# mippe_base.net
KiCad netlist of a schematic drawn in EAGLE
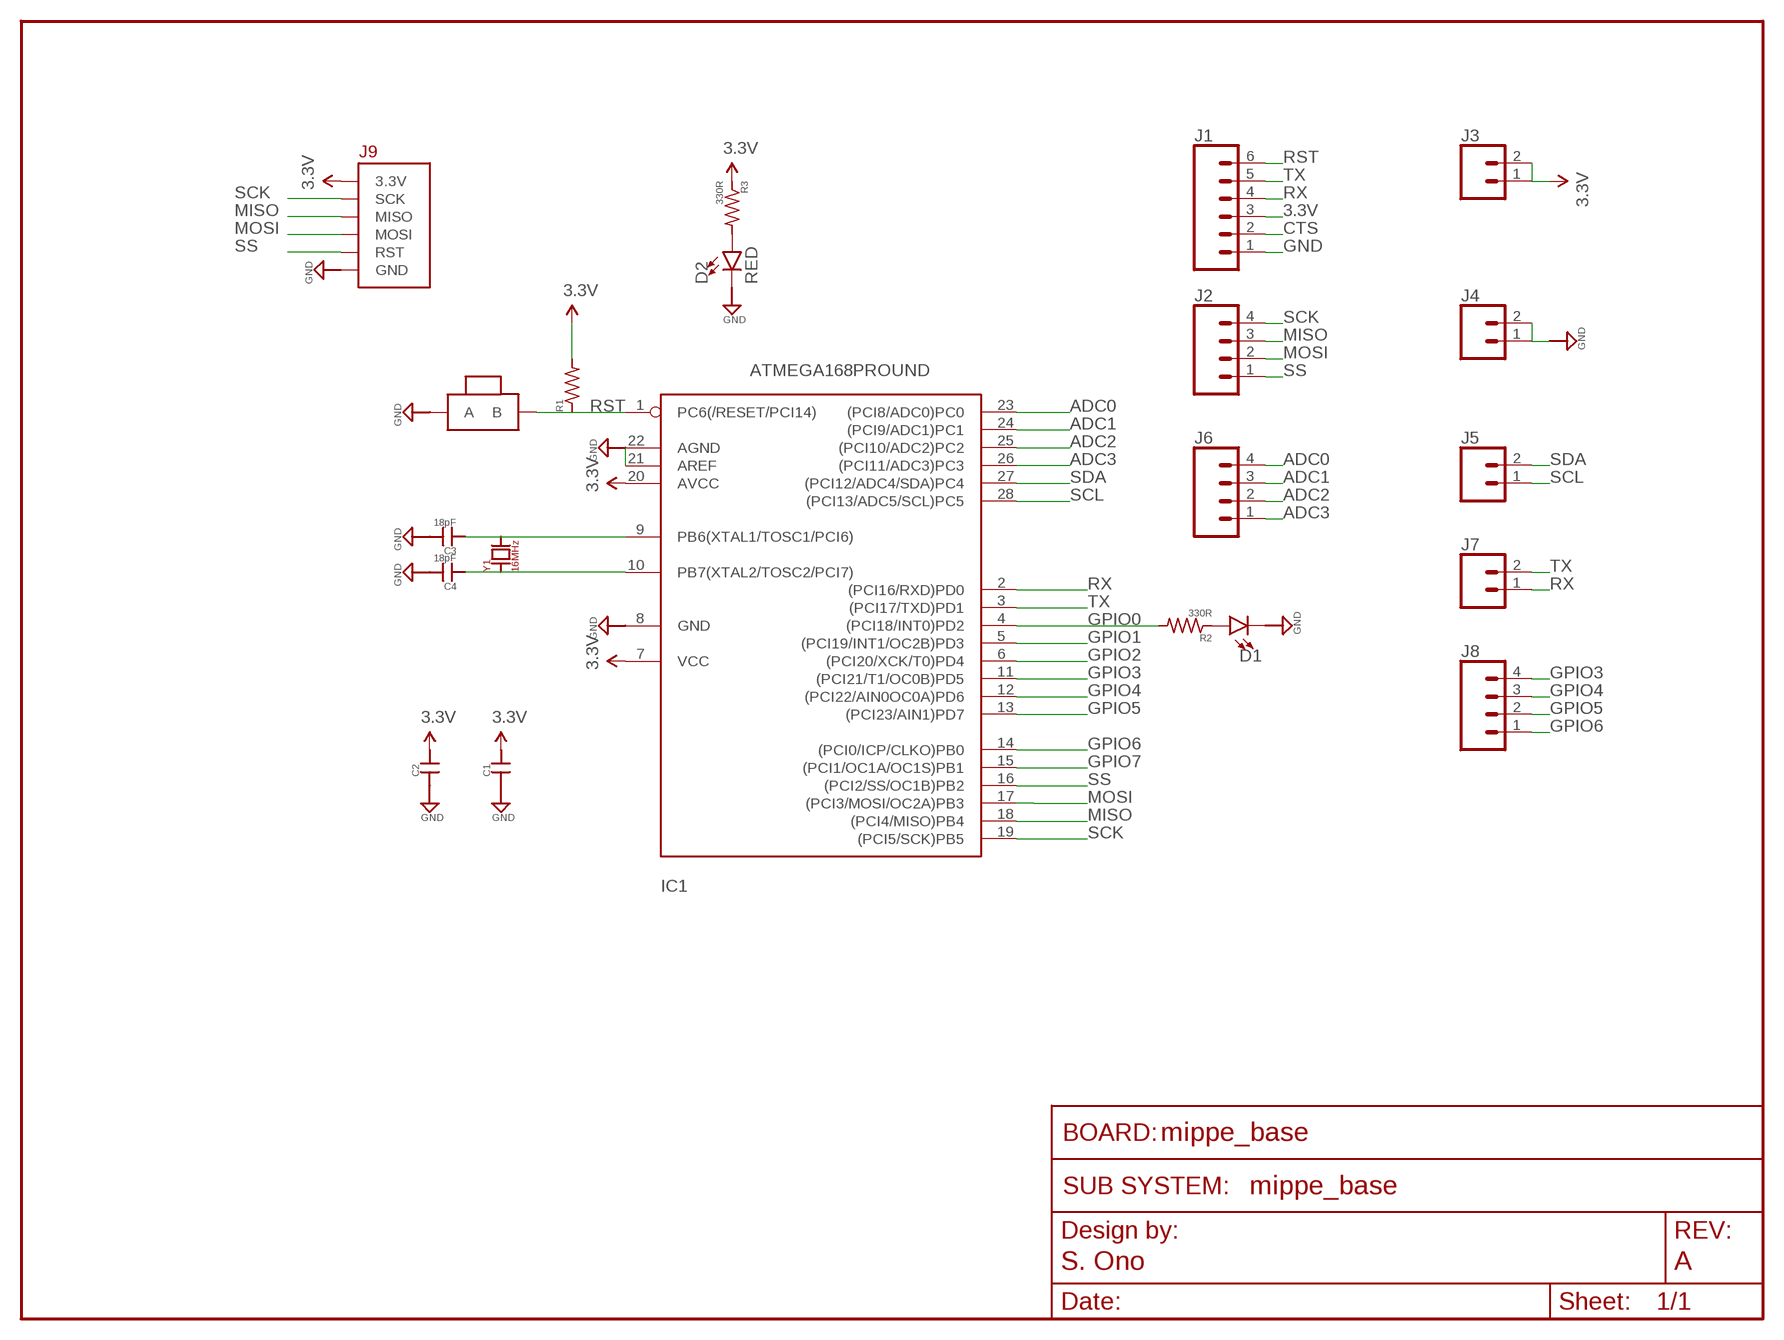
[diagram p0: schematic, sheet 1]

(export (version "E")
  (design (tool "Eeschema 10.0.6"))
  (components
    (comp (ref "C1")
      (value "CAP0603-CAP")
      (footprint "eagle-import:0603-CAP")
      (libsource (lib "eagle-import") (part "CAP0603-CAP"))
    )
    (comp (ref "C2")
      (value "CAP0603-CAP")
      (footprint "eagle-import:0603-CAP")
      (libsource (lib "eagle-import") (part "CAP0603-CAP"))
    )
    (comp (ref "C3")
      (value "18pF")
      (footprint "eagle-import:0603-CAP")
      (libsource (lib "eagle-import") (part "CAP0603-CAP"))
    )
    (comp (ref "C4")
      (value "18pF")
      (footprint "eagle-import:0603-CAP")
      (libsource (lib "eagle-import") (part "CAP0603-CAP"))
    )
    (comp (ref "D1")
      (value "LED0603")
      (footprint "eagle-import:LED-0603")
      (libsource (lib "eagle-import") (part "LED0603"))
    )
    (comp (ref "D2")
      (value "RED")
      (footprint "eagle-import:LED-0603")
      (libsource (lib "eagle-import") (part "LED0603"))
    )
    (comp (ref "IC1")
      (value "ATMEGA168PROUND")
      (footprint "eagle-import:DIL28-3-ROUND")
      (libsource (lib "eagle-import") (part "ATMEGA168PROUND"))
    )
    (comp (ref "J1")
      (value "CONN_06NO_SILK_FEMALE_PTH")
      (footprint "eagle-import:1X06_NO_SILK")
      (libsource (lib "eagle-import") (part "CONN_06NO_SILK_FEMALE_PTH"))
    )
    (comp (ref "J2")
      (value "CONN_041X04_NO_SILK")
      (footprint "eagle-import:1X04_NO_SILK")
      (libsource (lib "eagle-import") (part "CONN_041X04_NO_SILK"))
    )
    (comp (ref "J3")
      (value "CONN_021X02_NO_SILK")
      (footprint "eagle-import:1X02_NO_SILK")
      (libsource (lib "eagle-import") (part "CONN_021X02_NO_SILK"))
    )
    (comp (ref "J4")
      (value "CONN_021X02_NO_SILK")
      (footprint "eagle-import:1X02_NO_SILK")
      (libsource (lib "eagle-import") (part "CONN_021X02_NO_SILK"))
    )
    (comp (ref "J5")
      (value "CONN_021X02_NO_SILK")
      (footprint "eagle-import:1X02_NO_SILK")
      (libsource (lib "eagle-import") (part "CONN_021X02_NO_SILK"))
    )
    (comp (ref "J6")
      (value "CONN_041X04_NO_SILK")
      (footprint "eagle-import:1X04_NO_SILK")
      (libsource (lib "eagle-import") (part "CONN_041X04_NO_SILK"))
    )
    (comp (ref "J7")
      (value "CONN_021X02_NO_SILK")
      (footprint "eagle-import:1X02_NO_SILK")
      (libsource (lib "eagle-import") (part "CONN_021X02_NO_SILK"))
    )
    (comp (ref "J8")
      (value "CONN_041X04_NO_SILK")
      (footprint "eagle-import:1X04_NO_SILK")
      (libsource (lib "eagle-import") (part "CONN_041X04_NO_SILK"))
    )
    (comp (ref "J9")
      (value "BURNIN")
      (footprint "eagle-import:BURNIN")
      (libsource (lib "eagle-import") (part "BURNIN"))
    )
    (comp (ref "R1")
      (value "R-US_R0603")
      (footprint "eagle-import:R0603")
      (fields (field (name "MANUFACTURER") "Rohm Semiconductor"))
      (libsource (lib "eagle-import") (part "R-US_R0603"))
    )
    (comp (ref "R2")
      (value "330R")
      (footprint "eagle-import:R0603")
      (fields (field (name "MANUFACTURER") "Rohm Semiconductor"))
      (libsource (lib "eagle-import") (part "R-US_R0603"))
    )
    (comp (ref "R3")
      (value "330R")
      (footprint "eagle-import:R0603")
      (fields (field (name "MANUFACTURER") "Rohm Semiconductor"))
      (libsource (lib "eagle-import") (part "R-US_R0603"))
    )
    (comp (ref "SW1")
      (value "BTN-PTS810")
      (footprint "eagle-import:BTN_PTS810")
      (libsource (lib "eagle-import") (part "BTN-PTS810"))
    )
    (comp (ref "Y1")
      (value "16MHz")
      (footprint "eagle-import:HC-49")
      (libsource (lib "eagle-import") (part "CRYSTAL"))
    )
  )
  (nets
    (net (code "1") (name "/ADC0") (class "Default")
      (node (ref "IC1") (pin "23") (pinfunction "(PCI8/ADC0)PC0_23") (pintype "bidirectional"))
      (node (ref "J6") (pin "4") (pinfunction "4_4") (pintype "passive"))
    )
    (net (code "2") (name "/ADC1") (class "Default")
      (node (ref "IC1") (pin "24") (pinfunction "(PCI9/ADC1)PC1_24") (pintype "bidirectional"))
      (node (ref "J6") (pin "3") (pinfunction "3_3") (pintype "passive"))
    )
    (net (code "3") (name "/ADC2") (class "Default")
      (node (ref "IC1") (pin "25") (pinfunction "(PCI10/ADC2)PC2_25") (pintype "bidirectional"))
      (node (ref "J6") (pin "2") (pinfunction "2_2") (pintype "passive"))
    )
    (net (code "4") (name "/ADC3") (class "Default")
      (node (ref "IC1") (pin "26") (pinfunction "(PCI11/ADC3)PC3_26") (pintype "bidirectional"))
      (node (ref "J6") (pin "1") (pinfunction "1_1") (pintype "passive"))
    )
    (net (code "5") (name "/CTS") (class "Default")
      (node (ref "J1") (pin "2") (pinfunction "2_2") (pintype "passive"))
    )
    (net (code "6") (name "/GPIO0") (class "Default")
      (node (ref "IC1") (pin "4") (pinfunction "(PCI18/INT0)PD2_4") (pintype "bidirectional"))
      (node (ref "R2") (pin "2") (pinfunction "2_2") (pintype "passive"))
    )
    (net (code "7") (name "/GPIO1") (class "Default")
      (node (ref "IC1") (pin "5") (pinfunction "(PCI19/INT1/OC2B)PD3_5") (pintype "bidirectional"))
    )
    (net (code "8") (name "/GPIO2") (class "Default")
      (node (ref "IC1") (pin "6") (pinfunction "(PCI20/XCK/T0)PD4_6") (pintype "bidirectional"))
    )
    (net (code "9") (name "/GPIO3") (class "Default")
      (node (ref "IC1") (pin "11") (pinfunction "(PCI21/T1/OC0B)PD5_11") (pintype "bidirectional"))
      (node (ref "J8") (pin "4") (pinfunction "4_4") (pintype "passive"))
    )
    (net (code "10") (name "/GPIO4") (class "Default")
      (node (ref "IC1") (pin "12") (pinfunction "(PCI22/AIN0OC0A)PD6_12") (pintype "bidirectional"))
      (node (ref "J8") (pin "3") (pinfunction "3_3") (pintype "passive"))
    )
    (net (code "11") (name "/GPIO5") (class "Default")
      (node (ref "IC1") (pin "13") (pinfunction "(PCI23/AIN1)PD7_13") (pintype "bidirectional"))
      (node (ref "J8") (pin "2") (pinfunction "2_2") (pintype "passive"))
    )
    (net (code "12") (name "/GPIO6") (class "Default")
      (node (ref "IC1") (pin "14") (pinfunction "(PCI0/ICP/CLKO)PB0_14") (pintype "bidirectional"))
      (node (ref "J8") (pin "1") (pinfunction "1_1") (pintype "passive"))
    )
    (net (code "13") (name "/GPIO7") (class "Default")
      (node (ref "IC1") (pin "15") (pinfunction "(PCI1/OC1A/OC1S)PB1_15") (pintype "bidirectional"))
    )
    (net (code "14") (name "/MISO") (class "Default")
      (node (ref "IC1") (pin "18") (pinfunction "(PCI4/MISO)PB4_18") (pintype "bidirectional"))
      (node (ref "J2") (pin "3") (pinfunction "3_3") (pintype "passive"))
      (node (ref "J9") (pin "MISO") (pinfunction "MISO_MISO") (pintype "bidirectional"))
    )
    (net (code "15") (name "/MOSI") (class "Default")
      (node (ref "IC1") (pin "17") (pinfunction "(PCI3/MOSI/OC2A)PB3_17") (pintype "bidirectional"))
      (node (ref "J2") (pin "2") (pinfunction "2_2") (pintype "passive"))
      (node (ref "J9") (pin "MOSI") (pinfunction "MOSI_MOSI") (pintype "bidirectional"))
    )
    (net (code "16") (name "/RST") (class "Default")
      (node (ref "IC1") (pin "1") (pinfunction "PC6(/RESET/PCI14)_1") (pintype "bidirectional"))
      (node (ref "J1") (pin "6") (pinfunction "6_6") (pintype "passive"))
      (node (ref "R1") (pin "1") (pinfunction "1_1") (pintype "passive"))
      (node (ref "SW1") (pin "3") (pinfunction "B_3") (pintype "bidirectional"))
      (node (ref "SW1") (pin "4") (pinfunction "B_4") (pintype "bidirectional"))
    )
    (net (code "17") (name "/RX") (class "Default")
      (node (ref "IC1") (pin "2") (pinfunction "(PCI16/RXD)PD0_2") (pintype "bidirectional"))
      (node (ref "J1") (pin "4") (pinfunction "4_4") (pintype "passive"))
      (node (ref "J7") (pin "1") (pinfunction "1_1") (pintype "passive"))
    )
    (net (code "18") (name "/SCK") (class "Default")
      (node (ref "IC1") (pin "19") (pinfunction "(PCI5/SCK)PB5_19") (pintype "bidirectional"))
      (node (ref "J2") (pin "4") (pinfunction "4_4") (pintype "passive"))
      (node (ref "J9") (pin "SCK") (pinfunction "SCK_SCK") (pintype "bidirectional"))
    )
    (net (code "19") (name "/SCL") (class "Default")
      (node (ref "IC1") (pin "28") (pinfunction "(PCI13/ADC5/SCL)PC5_28") (pintype "bidirectional"))
      (node (ref "J5") (pin "1") (pinfunction "1_1") (pintype "passive"))
    )
    (net (code "20") (name "/SDA") (class "Default")
      (node (ref "IC1") (pin "27") (pinfunction "(PCI12/ADC4/SDA)PC4_27") (pintype "bidirectional"))
      (node (ref "J5") (pin "2") (pinfunction "2_2") (pintype "passive"))
    )
    (net (code "21") (name "/SS") (class "Default")
      (node (ref "IC1") (pin "16") (pinfunction "(PCI2/SS/OC1B)PB2_16") (pintype "bidirectional"))
      (node (ref "J2") (pin "1") (pinfunction "1_1") (pintype "passive"))
      (node (ref "J9") (pin "RST") (pinfunction "RST_RST") (pintype "bidirectional"))
    )
    (net (code "22") (name "/TX") (class "Default")
      (node (ref "IC1") (pin "3") (pinfunction "(PCI17/TXD)PD1_3") (pintype "bidirectional"))
      (node (ref "J1") (pin "5") (pinfunction "5_5") (pintype "passive"))
      (node (ref "J7") (pin "2") (pinfunction "2_2") (pintype "passive"))
    )
    (net (code "23") (name "3.3V") (class "Default")
      (node (ref "C1") (pin "2") (pinfunction "2_2") (pintype "passive"))
      (node (ref "C2") (pin "2") (pinfunction "2_2") (pintype "passive"))
      (node (ref "IC1") (pin "20") (pinfunction "AVCC_20") (pintype "bidirectional"))
      (node (ref "IC1") (pin "7") (pinfunction "VCC_7") (pintype "bidirectional"))
      (node (ref "J1") (pin "3") (pinfunction "3_3") (pintype "passive"))
      (node (ref "J3") (pin "1") (pinfunction "1_1") (pintype "passive"))
      (node (ref "J3") (pin "2") (pinfunction "2_2") (pintype "passive"))
      (node (ref "J9") (pin "3.3V") (pinfunction "3.3V_3.3V") (pintype "power_in"))
      (node (ref "R1") (pin "2") (pinfunction "2_2") (pintype "passive"))
      (node (ref "R3") (pin "1") (pinfunction "1_1") (pintype "passive"))
    )
    (net (code "24") (name "GND") (class "Default")
      (node (ref "C1") (pin "1") (pinfunction "1_1") (pintype "passive"))
      (node (ref "C2") (pin "1") (pinfunction "1_1") (pintype "passive"))
      (node (ref "C3") (pin "2") (pinfunction "2_2") (pintype "passive"))
      (node (ref "C4") (pin "2") (pinfunction "2_2") (pintype "passive"))
      (node (ref "D1") (pin "C") (pinfunction "C_C") (pintype "passive"))
      (node (ref "D2") (pin "C") (pinfunction "C_C") (pintype "passive"))
      (node (ref "IC1") (pin "21") (pinfunction "AREF_21") (pintype "bidirectional"))
      (node (ref "IC1") (pin "22") (pinfunction "AGND_22") (pintype "bidirectional"))
      (node (ref "IC1") (pin "8") (pinfunction "GND_8") (pintype "bidirectional"))
      (node (ref "J1") (pin "1") (pinfunction "1_1") (pintype "passive"))
      (node (ref "J4") (pin "1") (pinfunction "1_1") (pintype "passive"))
      (node (ref "J4") (pin "2") (pinfunction "2_2") (pintype "passive"))
      (node (ref "J9") (pin "GND") (pinfunction "GND_GND") (pintype "power_in"))
      (node (ref "SW1") (pin "1") (pinfunction "A_1") (pintype "bidirectional"))
      (node (ref "SW1") (pin "2") (pinfunction "A_2") (pintype "bidirectional"))
    )
    (net (code "25") (name "Net-(D1-PadA)") (class "Default")
      (node (ref "D1") (pin "A") (pinfunction "A_A") (pintype "passive"))
      (node (ref "R2") (pin "1") (pinfunction "1_1") (pintype "passive"))
    )
    (net (code "26") (name "Net-(D2-PadA)") (class "Default")
      (node (ref "D2") (pin "A") (pinfunction "A_A") (pintype "passive"))
      (node (ref "R3") (pin "2") (pinfunction "2_2") (pintype "passive"))
    )
    (net (code "27") (name "Net-(IC1-PB6(XTAL1{slash}TOSC1{slash}PCI6))") (class "Default")
      (node (ref "C3") (pin "1") (pinfunction "1_1") (pintype "passive"))
      (node (ref "IC1") (pin "9") (pinfunction "PB6(XTAL1/TOSC1/PCI6)_9") (pintype "bidirectional"))
      (node (ref "Y1") (pin "B") (pinfunction "B_B") (pintype "passive"))
    )
    (net (code "28") (name "Net-(IC1-PB7(XTAL2{slash}TOSC2{slash}PCI7))") (class "Default")
      (node (ref "C4") (pin "1") (pinfunction "1_1") (pintype "passive"))
      (node (ref "IC1") (pin "10") (pinfunction "PB7(XTAL2/TOSC2/PCI7)_10") (pintype "bidirectional"))
      (node (ref "Y1") (pin "A") (pinfunction "A_A") (pintype "passive"))
    )
  )
)
